# 67_Ethernet-GEPHY_RGMII0.net
KiCad netlist of a schematic drawn in Altium Designer
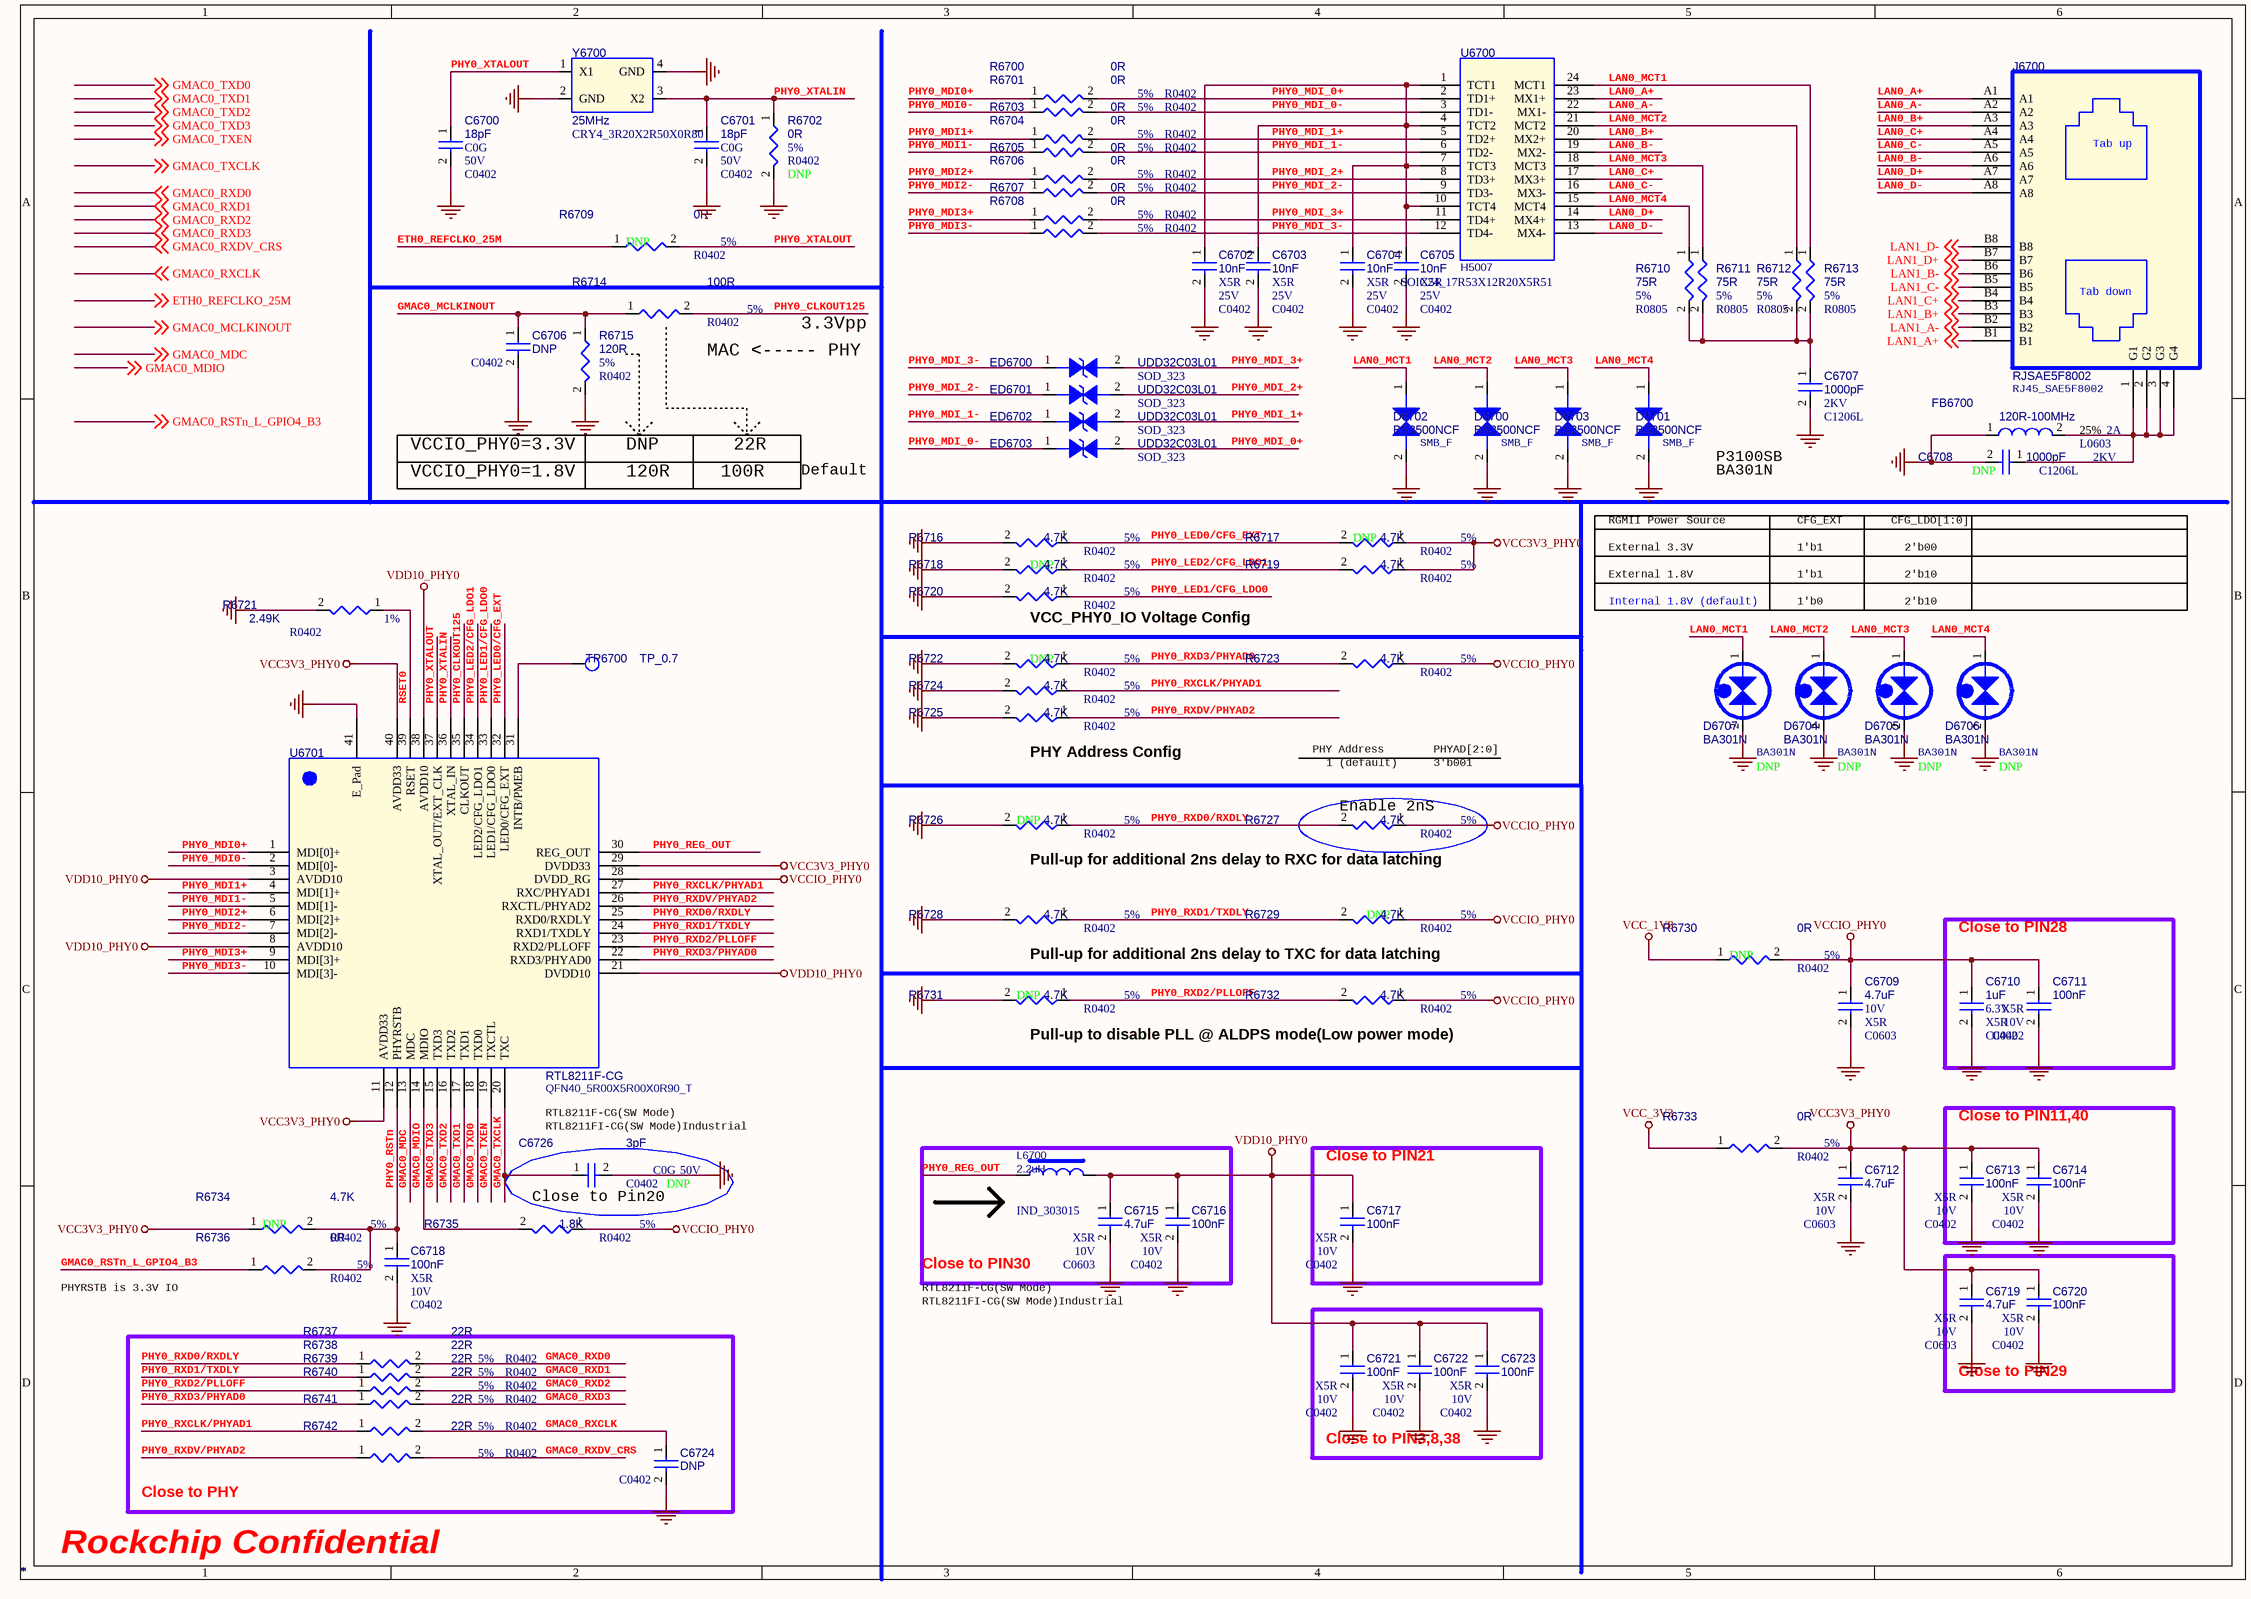
[diagram p0: 67.Ethernet-GEPHY_RGMII0.SchDoc]

(export (version "E")
  (design (tool "Eeschema 10.0.6"))
  (components
    (comp (ref "C6700")
      (value "*")
      (footprint "C0402")
      (description "cap,18.00pF,+/-5%,50V,C0G,C0402")
      (fields
        (field (name "VOLTAGE") "50V")
        (field (name "PCB FOOTPRINT") "C0402")
        (field (name "DIELECTRIC") "C0G")
        (field (name "TOLERANCE") "5%")
        (field (name "MANUFACTURER") "TDK")
        (field (name "ALTIUM_UNNAMED_1") "18pF")
        (field (name "CREATED BY") "JJJ")
      )
      (libsource (lib "*") (part "CAP NP"))
    )
    (comp (ref "C6701")
      (value "*")
      (footprint "C0402")
      (description "cap,18.00pF,+/-5%,50V,C0G,C0402")
      (fields
        (field (name "VOLTAGE") "50V")
        (field (name "PCB FOOTPRINT") "C0402")
        (field (name "DIELECTRIC") "C0G")
        (field (name "TOLERANCE") "5%")
        (field (name "MANUFACTURER") "TDK")
        (field (name "ALTIUM_UNNAMED_1") "18pF")
        (field (name "CREATED BY") "JJJ")
      )
      (libsource (lib "*") (part "CAP NP"))
    )
    (comp (ref "C6702")
      (value "*")
      (footprint "C0402")
      (description "cap,10.00nF,+/-10%,25V,X5R,C0402")
      (fields
        (field (name "VOLTAGE") "25V")
        (field (name "PCB FOOTPRINT") "C0402")
        (field (name "DIELECTRIC") "X5R")
        (field (name "TOLERANCE") "10%")
        (field (name "MANUFACTURER") "TDK")
        (field (name "ALTIUM_UNNAMED_1") "10nF")
        (field (name "CREATED BY") "JJJ")
      )
      (libsource (lib "*") (part "CAP NP"))
    )
    (comp (ref "C6703")
      (value "*")
      (footprint "C0402")
      (description "cap,10.00nF,+/-10%,25V,X5R,C0402")
      (fields
        (field (name "VOLTAGE") "25V")
        (field (name "PCB FOOTPRINT") "C0402")
        (field (name "DIELECTRIC") "X5R")
        (field (name "TOLERANCE") "10%")
        (field (name "MANUFACTURER") "TDK")
        (field (name "ALTIUM_UNNAMED_1") "10nF")
        (field (name "CREATED BY") "JJJ")
      )
      (libsource (lib "*") (part "CAP NP"))
    )
    (comp (ref "C6704")
      (value "*")
      (footprint "C0402")
      (description "cap,10.00nF,+/-10%,25V,X5R,C0402")
      (fields
        (field (name "VOLTAGE") "25V")
        (field (name "PCB FOOTPRINT") "C0402")
        (field (name "DIELECTRIC") "X5R")
        (field (name "MANUFACTURER") "TDK")
        (field (name "TOLERANCE") "10%")
        (field (name "ALTIUM_UNNAMED_1") "10nF")
        (field (name "CREATED BY") "JJJ")
      )
      (libsource (lib "*") (part "CAP NP"))
    )
    (comp (ref "C6705")
      (value "*")
      (footprint "C0402")
      (description "cap,10.00nF,+/-10%,25V,X5R,C0402")
      (fields
        (field (name "VOLTAGE") "25V")
        (field (name "PCB FOOTPRINT") "C0402")
        (field (name "DIELECTRIC") "X5R")
        (field (name "MANUFACTURER") "TDK")
        (field (name "TOLERANCE") "10%")
        (field (name "ALTIUM_UNNAMED_1") "10nF")
        (field (name "CREATED BY") "JJJ")
      )
      (libsource (lib "*") (part "CAP NP"))
    )
    (comp (ref "C6706")
      (value "*")
      (footprint "C0402")
      (description "Did Not Place.")
      (fields
        (field (name "PCB FOOTPRINT") "C0402")
        (field (name "ALTIUM_UNNAMED_1") "DNP")
        (field (name "CREATED BY") "JJJ")
      )
      (libsource (lib "*") (part "CAP NP"))
    )
    (comp (ref "C6707")
      (value "*")
      (footprint "C1206L")
      (description "ёЯС№µзИЭ,1000pF/2KV,C1206")
      (fields
        (field (name "VOLTAGE") "2KV")
        (field (name "PCB FOOTPRINT") "C1206L")
        (field (name "TOLERANCE") "20%")
        (field (name "ALTIUM_UNNAMED_1") "1000pF")
        (field (name "CREATED BY") "JJJ")
      )
      (libsource (lib "*") (part "CAP NP"))
    )
    (comp (ref "C6708")
      (value "*")
      (footprint "C1206L")
      (description "ёЯС№µзИЭ,1000pF/2KV,C1206")
      (fields
        (field (name "VOLTAGE") "2KV")
        (field (name "PCB FOOTPRINT") "C1206L")
        (field (name "TOLERANCE") "20%")
        (field (name "OPTION") "DNP")
        (field (name "ALTIUM_UNNAMED_1") "1000pF")
        (field (name "CREATED BY") "JJJ")
      )
      (libsource (lib "*") (part "CAP NP"))
    )
    (comp (ref "C6709")
      (value "*")
      (footprint "C0603")
      (description "cap,4.70uF,+/-10%,10V,X5R,C0603")
      (fields
        (field (name "VOLTAGE") "10V")
        (field (name "PCB FOOTPRINT") "C0603")
        (field (name "DIELECTRIC") "X5R")
        (field (name "TOLERANCE") "10%")
        (field (name "MANUFACTURER") "TDK")
        (field (name "ALTIUM_UNNAMED_1") "4.7uF")
        (field (name "CREATED BY") "JJJ")
      )
      (libsource (lib "*") (part "CAP NP"))
    )
    (comp (ref "C6710")
      (value "*")
      (footprint "C0402")
      (description "cap,1.00uF,+/-10%,6.3V,X5R,C0402")
      (fields
        (field (name "VOLTAGE") "6.3V")
        (field (name "PCB FOOTPRINT") "C0402")
        (field (name "DIELECTRIC") "X5R")
        (field (name "TOLERANCE") "10%")
        (field (name "MANUFACTURER") "TDK")
        (field (name "ALTIUM_UNNAMED_1") "1uF")
        (field (name "CREATED BY") "JJJ")
      )
      (libsource (lib "*") (part "CAP NP"))
    )
    (comp (ref "C6711")
      (value "*")
      (footprint "C0402")
      (description "cap,100.00nF,+/-10%,10V,X5R,C0402")
      (fields
        (field (name "VOLTAGE") "10V")
        (field (name "PCB FOOTPRINT") "C0402")
        (field (name "DIELECTRIC") "X5R")
        (field (name "TOLERANCE") "10%")
        (field (name "MANUFACTURER") "TDK")
        (field (name "ALTIUM_UNNAMED_1") "100nF")
        (field (name "CREATED BY") "JJJ")
      )
      (libsource (lib "*") (part "CAP NP"))
    )
    (comp (ref "C6712")
      (value "*")
      (footprint "C0603")
      (description "cap,4.70uF,+/-10%,10V,X5R,C0603")
      (fields
        (field (name "VOLTAGE") "10V")
        (field (name "PCB FOOTPRINT") "C0603")
        (field (name "DIELECTRIC") "X5R")
        (field (name "MANUFACTURER") "TDK")
        (field (name "TOLERANCE") "10%")
        (field (name "ALTIUM_UNNAMED_1") "4.7uF")
        (field (name "CREATED BY") "JJJ")
      )
      (libsource (lib "*") (part "CAP NP"))
    )
    (comp (ref "C6713")
      (value "*")
      (footprint "C0402")
      (description "cap,100.00nF,+/-10%,10V,X5R,C0402")
      (fields
        (field (name "VOLTAGE") "10V")
        (field (name "PCB FOOTPRINT") "C0402")
        (field (name "DIELECTRIC") "X5R")
        (field (name "TOLERANCE") "10%")
        (field (name "MANUFACTURER") "TDK")
        (field (name "ALTIUM_UNNAMED_1") "100nF")
        (field (name "CREATED BY") "JJJ")
      )
      (libsource (lib "*") (part "CAP NP"))
    )
    (comp (ref "C6714")
      (value "*")
      (footprint "C0402")
      (description "cap,100.00nF,+/-10%,10V,X5R,C0402")
      (fields
        (field (name "VOLTAGE") "10V")
        (field (name "PCB FOOTPRINT") "C0402")
        (field (name "DIELECTRIC") "X5R")
        (field (name "TOLERANCE") "10%")
        (field (name "MANUFACTURER") "TDK")
        (field (name "ALTIUM_UNNAMED_1") "100nF")
        (field (name "CREATED BY") "JJJ")
      )
      (libsource (lib "*") (part "CAP NP"))
    )
    (comp (ref "C6715")
      (value "*")
      (footprint "C0603")
      (description "cap,4.70uF,+/-10%,10V,X5R,C0603")
      (fields
        (field (name "VOLTAGE") "10V")
        (field (name "PCB FOOTPRINT") "C0603")
        (field (name "DIELECTRIC") "X5R")
        (field (name "MANUFACTURER") "TDK")
        (field (name "TOLERANCE") "10%")
        (field (name "ALTIUM_UNNAMED_1") "4.7uF")
        (field (name "CREATED BY") "JJJ")
      )
      (libsource (lib "*") (part "CAP NP"))
    )
    (comp (ref "C6716")
      (value "*")
      (footprint "C0402")
      (description "cap,100.00nF,+/-10%,10V,X5R,C0402")
      (fields
        (field (name "VOLTAGE") "10V")
        (field (name "PCB FOOTPRINT") "C0402")
        (field (name "DIELECTRIC") "X5R")
        (field (name "MANUFACTURER") "TDK")
        (field (name "TOLERANCE") "10%")
        (field (name "ALTIUM_UNNAMED_1") "100nF")
        (field (name "CREATED BY") "JJJ")
      )
      (libsource (lib "*") (part "CAP NP"))
    )
    (comp (ref "C6717")
      (value "*")
      (footprint "C0402")
      (description "cap,100.00nF,+/-10%,10V,X5R,C0402")
      (fields
        (field (name "VOLTAGE") "10V")
        (field (name "PCB FOOTPRINT") "C0402")
        (field (name "DIELECTRIC") "X5R")
        (field (name "MANUFACTURER") "TDK")
        (field (name "TOLERANCE") "10%")
        (field (name "ALTIUM_UNNAMED_1") "100nF")
        (field (name "CREATED BY") "JJJ")
      )
      (libsource (lib "*") (part "CAP NP"))
    )
    (comp (ref "C6718")
      (value "*")
      (footprint "C0402")
      (description "cap,100.00nF,+/-10%,10V,X5R,C0402")
      (fields
        (field (name "VOLTAGE") "10V")
        (field (name "PCB FOOTPRINT") "C0402")
        (field (name "DIELECTRIC") "X5R")
        (field (name "MANUFACTURER") "TDK")
        (field (name "TOLERANCE") "10%")
        (field (name "ALTIUM_UNNAMED_1") "100nF")
        (field (name "CREATED BY") "JJJ")
      )
      (libsource (lib "*") (part "CAP NP"))
    )
    (comp (ref "C6719")
      (value "*")
      (footprint "C0603")
      (description "cap,4.70uF,+/-10%,10V,X5R,C0603")
      (fields
        (field (name "VOLTAGE") "10V")
        (field (name "PCB FOOTPRINT") "C0603")
        (field (name "DIELECTRIC") "X5R")
        (field (name "MANUFACTURER") "TDK")
        (field (name "TOLERANCE") "10%")
        (field (name "ALTIUM_UNNAMED_1") "4.7uF")
        (field (name "CREATED BY") "JJJ")
      )
      (libsource (lib "*") (part "CAP NP"))
    )
    (comp (ref "C6720")
      (value "*")
      (footprint "C0402")
      (description "cap,100.00nF,+/-10%,10V,X5R,C0402")
      (fields
        (field (name "VOLTAGE") "10V")
        (field (name "PCB FOOTPRINT") "C0402")
        (field (name "DIELECTRIC") "X5R")
        (field (name "TOLERANCE") "10%")
        (field (name "MANUFACTURER") "TDK")
        (field (name "ALTIUM_UNNAMED_1") "100nF")
        (field (name "CREATED BY") "JJJ")
      )
      (libsource (lib "*") (part "CAP NP"))
    )
    (comp (ref "C6721")
      (value "*")
      (footprint "C0402")
      (description "cap,100.00nF,+/-10%,10V,X5R,C0402")
      (fields
        (field (name "VOLTAGE") "10V")
        (field (name "PCB FOOTPRINT") "C0402")
        (field (name "DIELECTRIC") "X5R")
        (field (name "TOLERANCE") "10%")
        (field (name "MANUFACTURER") "TDK")
        (field (name "ALTIUM_UNNAMED_1") "100nF")
        (field (name "CREATED BY") "JJJ")
      )
      (libsource (lib "*") (part "CAP NP"))
    )
    (comp (ref "C6722")
      (value "*")
      (footprint "C0402")
      (description "cap,100.00nF,+/-10%,10V,X5R,C0402")
      (fields
        (field (name "VOLTAGE") "10V")
        (field (name "PCB FOOTPRINT") "C0402")
        (field (name "DIELECTRIC") "X5R")
        (field (name "TOLERANCE") "10%")
        (field (name "MANUFACTURER") "TDK")
        (field (name "ALTIUM_UNNAMED_1") "100nF")
        (field (name "CREATED BY") "JJJ")
      )
      (libsource (lib "*") (part "CAP NP"))
    )
    (comp (ref "C6723")
      (value "*")
      (footprint "C0402")
      (description "cap,100.00nF,+/-10%,10V,X5R,C0402")
      (fields
        (field (name "VOLTAGE") "10V")
        (field (name "PCB FOOTPRINT") "C0402")
        (field (name "DIELECTRIC") "X5R")
        (field (name "TOLERANCE") "10%")
        (field (name "MANUFACTURER") "TDK")
        (field (name "ALTIUM_UNNAMED_1") "100nF")
        (field (name "CREATED BY") "JJJ")
      )
      (libsource (lib "*") (part "CAP NP"))
    )
    (comp (ref "C6724")
      (value "*")
      (footprint "C0402")
      (description "Did Not Place.")
      (fields
        (field (name "PCB FOOTPRINT") "C0402")
        (field (name "ALTIUM_UNNAMED_1") "DNP")
        (field (name "CREATED BY") "JJJ")
      )
      (libsource (lib "*") (part "CAP NP"))
    )
    (comp (ref "C6726")
      (value "*")
      (footprint "C0402")
      (description "cap,3.00pF,+/-0.25,50V,C0G,C0402")
      (fields
        (field (name "VOLTAGE") "50V")
        (field (name "PCB FOOTPRINT") "C0402")
        (field (name "DIELECTRIC") "C0G")
        (field (name "TOLERANCE") "+/-0.25pF")
        (field (name "MANUFACTURER") "TDK")
        (field (name "OPTION") "DNP")
        (field (name "ALTIUM_UNNAMED_1") "3pF")
        (field (name "CREATED BY") "JJJ")
      )
      (libsource (lib "*") (part "CAP NP"))
    )
    (comp (ref "D6700")
      (value "*")
      (footprint "BA301N")
      (fields (field (name "PCB FOOTPRINT") "SMB_F") (field (name "ALTIUM_UNNAMED_1") "BS3500NCF"))
      (libsource (lib "*") (part "BA301N_3"))
    )
    (comp (ref "D6701")
      (value "*")
      (footprint "BA301N")
      (fields (field (name "PCB FOOTPRINT") "SMB_F") (field (name "ALTIUM_UNNAMED_1") "BS3500NCF"))
      (libsource (lib "*") (part "BA301N_3"))
    )
    (comp (ref "D6702")
      (value "*")
      (footprint "BA301N")
      (fields (field (name "PCB FOOTPRINT") "SMB_F") (field (name "ALTIUM_UNNAMED_1") "BS3500NCF"))
      (libsource (lib "*") (part "BA301N_3"))
    )
    (comp (ref "D6703")
      (value "*")
      (footprint "BA301N")
      (fields (field (name "PCB FOOTPRINT") "SMB_F") (field (name "ALTIUM_UNNAMED_1") "BS3500NCF"))
      (libsource (lib "*") (part "BA301N_3"))
    )
    (comp (ref "D6704")
      (value "*")
      (footprint "BA301N")
      (fields
        (field (name "OPTION") "DNP")
        (field (name "PCB FOOTPRINT") "BA301N")
        (field (name "ALTIUM_UNNAMED_1") "BA301N")
      )
      (libsource (lib "*") (part "BA301N_1"))
    )
    (comp (ref "D6705")
      (value "*")
      (footprint "BA301N")
      (fields
        (field (name "OPTION") "DNP")
        (field (name "PCB FOOTPRINT") "BA301N")
        (field (name "ALTIUM_UNNAMED_1") "BA301N")
      )
      (libsource (lib "*") (part "BA301N_1"))
    )
    (comp (ref "D6706")
      (value "*")
      (footprint "BA301N")
      (fields
        (field (name "OPTION") "DNP")
        (field (name "PCB FOOTPRINT") "BA301N")
        (field (name "ALTIUM_UNNAMED_1") "BA301N")
      )
      (libsource (lib "*") (part "BA301N_1"))
    )
    (comp (ref "D6707")
      (value "*")
      (footprint "BA301N")
      (fields
        (field (name "OPTION") "DNP")
        (field (name "PCB FOOTPRINT") "BA301N")
        (field (name "ALTIUM_UNNAMED_1") "BA301N")
      )
      (libsource (lib "*") (part "BA301N_1"))
    )
    (comp (ref "ED6700")
      (value "*")
      (footprint "SOD_323")
      (description "Transient Voltage Suppressor,0.8pF")
      (fields
        (field (name "PCB FOOTPRINT") "SOD_323")
        (field (name "MANUFACTURER") "WillSemi(О¤¶ы°лµјМе)")
        (field (name "ALTIUM_UNNAMED_1") "UDD32C03L01")
        (field (name "CREATED BY") "JJJ")
      )
      (libsource (lib "*") (part "DIODE BI_DIR TRIG"))
    )
    (comp (ref "ED6701")
      (value "*")
      (footprint "SOD_323")
      (description "Transient Voltage Suppressor,0.8pF")
      (fields
        (field (name "PCB FOOTPRINT") "SOD_323")
        (field (name "MANUFACTURER") "WillSemi(О¤¶ы°лµјМе)")
        (field (name "ALTIUM_UNNAMED_1") "UDD32C03L01")
        (field (name "CREATED BY") "JJJ")
      )
      (libsource (lib "*") (part "DIODE BI_DIR TRIG"))
    )
    (comp (ref "ED6702")
      (value "*")
      (footprint "SOD_323")
      (description "Transient Voltage Suppressor,0.8pF")
      (fields
        (field (name "PCB FOOTPRINT") "SOD_323")
        (field (name "MANUFACTURER") "WillSemi(О¤¶ы°лµјМе)")
        (field (name "ALTIUM_UNNAMED_1") "UDD32C03L01")
        (field (name "CREATED BY") "JJJ")
      )
      (libsource (lib "*") (part "DIODE BI_DIR TRIG"))
    )
    (comp (ref "ED6703")
      (value "*")
      (footprint "SOD_323")
      (description "Transient Voltage Suppressor,0.8pF")
      (fields
        (field (name "PCB FOOTPRINT") "SOD_323")
        (field (name "MANUFACTURER") "WillSemi(О¤¶ы°лµјМе)")
        (field (name "ALTIUM_UNNAMED_1") "UDD32C03L01")
        (field (name "CREATED BY") "JJJ")
      )
      (libsource (lib "*") (part "DIODE BI_DIR TRIG"))
    )
    (comp (ref "FB6700")
      (value "*")
      (footprint "L0603")
      (description "BEAD,120R@100MHz,current=2000mA,0603")
      (fields
        (field (name "TOLERANCE") "25%")
        (field (name "PCB FOOTPRINT") "L0603")
        (field (name "IRMS") "2A")
        (field (name "MANUFACTURER") "Murata")
        (field (name "ALTIUM_UNNAMED_1") "120R-100MHz")
        (field (name "CREATED BY") "DZS")
      )
      (libsource (lib "*") (part "BEAD"))
    )
    (comp (ref "J6700")
      (value "*")
      (footprint "RJSAE5F8002")
      (fields (field (name "PCB FOOTPRINT") "RJ45_SAE5F8002") (field (name "ALTIUM_UNNAMED_1") "RJSAE5F8002"))
      (libsource (lib "*") (part "RJSAE5F8002"))
    )
    (comp (ref "L6700")
      (value "*")
      (footprint "IND_303015")
      (description "Power Inductor,2.2uH,0.3,IND_303015")
      (fields
        (field (name "PCB FOOTPRINT") "IND_303015")
        (field (name "MANUFACTURER") "sunlord")
        (field (name "TOLERANCE") "30%")
        (field (name "ALTIUM_UNNAMED_1") "2.2uH")
        (field (name "CREATED BY") "YTL")
      )
      (libsource (lib "*") (part "INDUCTORS OF FERRITE_Dup1"))
    )
    (comp (ref "R6700")
      (value "*")
      (footprint "R0402")
      (description "НЁУГєсД¤µзЧи,0R,+/-5%,R0402,1/16W.")
      (fields
        (field (name "PCB FOOTPRINT") "R0402")
        (field (name "TOLERANCE") "5%")
        (field (name "MANUFACTURER") "YAGEO")
        (field (name "ALTIUM_UNNAMED_1") "0R")
        (field (name "CREATED BY") "YTL")
      )
      (libsource (lib "*") (part "RESISTOR_Dup1"))
    )
    (comp (ref "R6701")
      (value "*")
      (footprint "R0402")
      (description "НЁУГєсД¤µзЧи,0R,+/-5%,R0402,1/16W.")
      (fields
        (field (name "PCB FOOTPRINT") "R0402")
        (field (name "TOLERANCE") "5%")
        (field (name "MANUFACTURER") "YAGEO")
        (field (name "ALTIUM_UNNAMED_1") "0R")
        (field (name "CREATED BY") "YTL")
      )
      (libsource (lib "*") (part "RESISTOR_Dup1"))
    )
    (comp (ref "R6702")
      (value "*")
      (footprint "R0402")
      (description "НЁУГєсД¤µзЧи,0R,+/-5%,R0402,1/16W.")
      (fields
        (field (name "PCB FOOTPRINT") "R0402")
        (field (name "TOLERANCE") "5%")
        (field (name "MANUFACTURER") "YAGEO")
        (field (name "OPTION") "DNP")
        (field (name "ALTIUM_UNNAMED_1") "0R")
        (field (name "CREATED BY") "YTL")
      )
      (libsource (lib "*") (part "RESISTOR_Dup1"))
    )
    (comp (ref "R6703")
      (value "*")
      (footprint "R0402")
      (description "НЁУГєсД¤µзЧи,0R,+/-5%,R0402,1/16W.")
      (fields
        (field (name "PCB FOOTPRINT") "R0402")
        (field (name "TOLERANCE") "5%")
        (field (name "MANUFACTURER") "YAGEO")
        (field (name "ALTIUM_UNNAMED_1") "0R")
        (field (name "CREATED BY") "YTL")
      )
      (libsource (lib "*") (part "RESISTOR_Dup1"))
    )
    (comp (ref "R6704")
      (value "*")
      (footprint "R0402")
      (description "НЁУГєсД¤µзЧи,0R,+/-5%,R0402,1/16W.")
      (fields
        (field (name "PCB FOOTPRINT") "R0402")
        (field (name "TOLERANCE") "5%")
        (field (name "MANUFACTURER") "YAGEO")
        (field (name "ALTIUM_UNNAMED_1") "0R")
        (field (name "CREATED BY") "YTL")
      )
      (libsource (lib "*") (part "RESISTOR_Dup1"))
    )
    (comp (ref "R6705")
      (value "*")
      (footprint "R0402")
      (description "НЁУГєсД¤µзЧи,0R,+/-5%,R0402,1/16W.")
      (fields
        (field (name "PCB FOOTPRINT") "R0402")
        (field (name "TOLERANCE") "5%")
        (field (name "MANUFACTURER") "YAGEO")
        (field (name "ALTIUM_UNNAMED_1") "0R")
        (field (name "CREATED BY") "YTL")
      )
      (libsource (lib "*") (part "RESISTOR_Dup1"))
    )
    (comp (ref "R6706")
      (value "*")
      (footprint "R0402")
      (description "НЁУГєсД¤µзЧи,0R,+/-5%,R0402,1/16W.")
      (fields
        (field (name "PCB FOOTPRINT") "R0402")
        (field (name "TOLERANCE") "5%")
        (field (name "MANUFACTURER") "YAGEO")
        (field (name "ALTIUM_UNNAMED_1") "0R")
        (field (name "CREATED BY") "YTL")
      )
      (libsource (lib "*") (part "RESISTOR_Dup1"))
    )
    (comp (ref "R6707")
      (value "*")
      (footprint "R0402")
      (description "НЁУГєсД¤µзЧи,0R,+/-5%,R0402,1/16W.")
      (fields
        (field (name "PCB FOOTPRINT") "R0402")
        (field (name "TOLERANCE") "5%")
        (field (name "MANUFACTURER") "YAGEO")
        (field (name "ALTIUM_UNNAMED_1") "0R")
        (field (name "CREATED BY") "YTL")
      )
      (libsource (lib "*") (part "RESISTOR_Dup1"))
    )
    (comp (ref "R6708")
      (value "*")
      (footprint "R0402")
      (description "НЁУГєсД¤µзЧи,0R,+/-5%,R0402,1/16W.")
      (fields
        (field (name "PCB FOOTPRINT") "R0402")
        (field (name "TOLERANCE") "5%")
        (field (name "MANUFACTURER") "YAGEO")
        (field (name "ALTIUM_UNNAMED_1") "0R")
        (field (name "CREATED BY") "YTL")
      )
      (libsource (lib "*") (part "RESISTOR_Dup1"))
    )
    (comp (ref "R6709")
      (value "*")
      (footprint "R0402")
      (description "НЁУГєсД¤µзЧи,0R,+/-5%,R0402,1/16W.")
      (fields
        (field (name "PCB FOOTPRINT") "R0402")
        (field (name "TOLERANCE") "5%")
        (field (name "OPTION") "DNP")
        (field (name "MANUFACTURER") "YAGEO")
        (field (name "ALTIUM_UNNAMED_1") "0R")
        (field (name "CREATED BY") "YTL")
      )
      (libsource (lib "*") (part "RESISTOR_Dup1"))
    )
    (comp (ref "R6710")
      (value "*")
      (footprint "R0402")
      (description "НЁУГєсД¤µзЧи,75R,+/-5%,R0805,1/8W.")
      (fields
        (field (name "PCB FOOTPRINT") "R0805")
        (field (name "TOLERANCE") "5%")
        (field (name "MANUFACTURER") "YAGEO")
        (field (name "ALTIUM_UNNAMED_1") "75R")
        (field (name "CREATED BY") "YTL")
      )
      (libsource (lib "*") (part "RESISTOR_Dup1"))
    )
    (comp (ref "R6711")
      (value "*")
      (footprint "R0402")
      (description "НЁУГєсД¤µзЧи,75R,+/-5%,R0805,1/8W.")
      (fields
        (field (name "PCB FOOTPRINT") "R0805")
        (field (name "TOLERANCE") "5%")
        (field (name "MANUFACTURER") "YAGEO")
        (field (name "ALTIUM_UNNAMED_1") "75R")
        (field (name "CREATED BY") "YTL")
      )
      (libsource (lib "*") (part "RESISTOR_Dup1"))
    )
    (comp (ref "R6712")
      (value "*")
      (footprint "R0402")
      (description "НЁУГєсД¤µзЧи,75R,+/-5%,R0805,1/8W.")
      (fields
        (field (name "PCB FOOTPRINT") "R0805")
        (field (name "TOLERANCE") "5%")
        (field (name "MANUFACTURER") "YAGEO")
        (field (name "ALTIUM_UNNAMED_1") "75R")
        (field (name "CREATED BY") "YTL")
      )
      (libsource (lib "*") (part "RESISTOR_Dup1"))
    )
    (comp (ref "R6713")
      (value "*")
      (footprint "R0402")
      (description "НЁУГєсД¤µзЧи,75R,+/-5%,R0805,1/8W.")
      (fields
        (field (name "PCB FOOTPRINT") "R0805")
        (field (name "TOLERANCE") "5%")
        (field (name "MANUFACTURER") "YAGEO")
        (field (name "ALTIUM_UNNAMED_1") "75R")
        (field (name "CREATED BY") "YTL")
      )
      (libsource (lib "*") (part "RESISTOR_Dup1"))
    )
    (comp (ref "R6714")
      (value "*")
      (footprint "R0402")
      (description "НЁУГєсД¤µзЧи,100R,+/-5%,R0402,1/16W.")
      (fields
        (field (name "PCB FOOTPRINT") "R0402")
        (field (name "TOLERANCE") "5%")
        (field (name "MANUFACTURER") "YAGEO")
        (field (name "ALTIUM_UNNAMED_1") "100R")
        (field (name "CREATED BY") "YTL")
      )
      (libsource (lib "*") (part "RESISTOR_Dup1"))
    )
    (comp (ref "R6715")
      (value "*")
      (footprint "R0402")
      (description "НЁУГєсД¤µзЧи,120R,+/-5%,R0402,1/16W.")
      (fields
        (field (name "PCB FOOTPRINT") "R0402")
        (field (name "TOLERANCE") "5%")
        (field (name "MANUFACTURER") "YAGEO")
        (field (name "ALTIUM_UNNAMED_1") "120R")
        (field (name "CREATED BY") "YTL")
      )
      (libsource (lib "*") (part "RESISTOR_Dup1"))
    )
    (comp (ref "R6716")
      (value "*")
      (footprint "R0402")
      (description "НЁУГєсД¤µзЧи,4K7,+/-5%,R0402,1/16W.")
      (fields
        (field (name "PCB FOOTPRINT") "R0402")
        (field (name "TOLERANCE") "5%")
        (field (name "MANUFACTURER") "YAGEO")
        (field (name "ALTIUM_UNNAMED_1") "4.7K")
        (field (name "CREATED BY") "YTL")
      )
      (libsource (lib "*") (part "RESISTOR_Dup1"))
    )
    (comp (ref "R6717")
      (value "*")
      (footprint "R0402")
      (description "НЁУГєсД¤µзЧи,4K7,+/-5%,R0402,1/16W.")
      (fields
        (field (name "PCB FOOTPRINT") "R0402")
        (field (name "TOLERANCE") "5%")
        (field (name "MANUFACTURER") "YAGEO")
        (field (name "OPTION") "DNP")
        (field (name "ALTIUM_UNNAMED_1") "4.7K")
        (field (name "CREATED BY") "YTL")
      )
      (libsource (lib "*") (part "RESISTOR_Dup1"))
    )
    (comp (ref "R6718")
      (value "*")
      (footprint "R0402")
      (description "НЁУГєсД¤µзЧи,4K7,+/-5%,R0402,1/16W.")
      (fields
        (field (name "PCB FOOTPRINT") "R0402")
        (field (name "TOLERANCE") "5%")
        (field (name "OPTION") "DNP")
        (field (name "MANUFACTURER") "YAGEO")
        (field (name "ALTIUM_UNNAMED_1") "4.7K")
        (field (name "CREATED BY") "YTL")
      )
      (libsource (lib "*") (part "RESISTOR_Dup1"))
    )
    (comp (ref "R6719")
      (value "*")
      (footprint "R0402")
      (description "НЁУГєсД¤µзЧи,4K7,+/-5%,R0402,1/16W.")
      (fields
        (field (name "PCB FOOTPRINT") "R0402")
        (field (name "TOLERANCE") "5%")
        (field (name "MANUFACTURER") "YAGEO")
        (field (name "ALTIUM_UNNAMED_1") "4.7K")
        (field (name "CREATED BY") "YTL")
      )
      (libsource (lib "*") (part "RESISTOR_Dup1"))
    )
    (comp (ref "R6720")
      (value "*")
      (footprint "R0402")
      (description "НЁУГєсД¤µзЧи,4K7,+/-5%,R0402,1/16W.")
      (fields
        (field (name "PCB FOOTPRINT") "R0402")
        (field (name "TOLERANCE") "5%")
        (field (name "MANUFACTURER") "YAGEO")
        (field (name "ALTIUM_UNNAMED_1") "4.7K")
        (field (name "CREATED BY") "YTL")
      )
      (libsource (lib "*") (part "RESISTOR_Dup1"))
    )
    (comp (ref "R6721")
      (value "*")
      (footprint "R0402")
      (description "НЁУГєсД¤µзЧи,2K49,+/-1%,R0402,1/16W.")
      (fields
        (field (name "PCB FOOTPRINT") "R0402")
        (field (name "TOLERANCE") "1%")
        (field (name "MANUFACTURER") "YAGEO")
        (field (name "ALTIUM_UNNAMED_1") "2.49K")
        (field (name "CREATED BY") "YTL")
      )
      (libsource (lib "*") (part "RESISTOR_Dup1"))
    )
    (comp (ref "R6722")
      (value "*")
      (footprint "R0402")
      (description "НЁУГєсД¤µзЧи,4K7,+/-5%,R0402,1/16W.")
      (fields
        (field (name "PCB FOOTPRINT") "R0402")
        (field (name "TOLERANCE") "5%")
        (field (name "OPTION") "DNP")
        (field (name "MANUFACTURER") "YAGEO")
        (field (name "ALTIUM_UNNAMED_1") "4.7K")
        (field (name "CREATED BY") "YTL")
      )
      (libsource (lib "*") (part "RESISTOR_Dup1"))
    )
    (comp (ref "R6723")
      (value "*")
      (footprint "R0402")
      (description "НЁУГєсД¤µзЧи,4K7,+/-5%,R0402,1/16W.")
      (fields
        (field (name "PCB FOOTPRINT") "R0402")
        (field (name "TOLERANCE") "5%")
        (field (name "MANUFACTURER") "YAGEO")
        (field (name "ALTIUM_UNNAMED_1") "4.7K")
        (field (name "CREATED BY") "YTL")
      )
      (libsource (lib "*") (part "RESISTOR_Dup1"))
    )
    (comp (ref "R6724")
      (value "*")
      (footprint "R0402")
      (description "НЁУГєсД¤µзЧи,4K7,+/-5%,R0402,1/16W.")
      (fields
        (field (name "PCB FOOTPRINT") "R0402")
        (field (name "TOLERANCE") "5%")
        (field (name "MANUFACTURER") "YAGEO")
        (field (name "ALTIUM_UNNAMED_1") "4.7K")
        (field (name "CREATED BY") "YTL")
      )
      (libsource (lib "*") (part "RESISTOR_Dup1"))
    )
    (comp (ref "R6725")
      (value "*")
      (footprint "R0402")
      (description "НЁУГєсД¤µзЧи,4K7,+/-5%,R0402,1/16W.")
      (fields
        (field (name "PCB FOOTPRINT") "R0402")
        (field (name "TOLERANCE") "5%")
        (field (name "MANUFACTURER") "YAGEO")
        (field (name "ALTIUM_UNNAMED_1") "4.7K")
        (field (name "CREATED BY") "YTL")
      )
      (libsource (lib "*") (part "RESISTOR_Dup1"))
    )
    (comp (ref "R6726")
      (value "*")
      (footprint "R0402")
      (description "НЁУГєсД¤µзЧи,4K7,+/-5%,R0402,1/16W.")
      (fields
        (field (name "PCB FOOTPRINT") "R0402")
        (field (name "TOLERANCE") "5%")
        (field (name "OPTION") "DNP")
        (field (name "MANUFACTURER") "YAGEO")
        (field (name "ALTIUM_UNNAMED_1") "4.7K")
        (field (name "CREATED BY") "YTL")
      )
      (libsource (lib "*") (part "RESISTOR_Dup1"))
    )
    (comp (ref "R6727")
      (value "*")
      (footprint "R0402")
      (description "НЁУГєсД¤µзЧи,4K7,+/-5%,R0402,1/16W.")
      (fields
        (field (name "PCB FOOTPRINT") "R0402")
        (field (name "TOLERANCE") "5%")
        (field (name "MANUFACTURER") "YAGEO")
        (field (name "ALTIUM_UNNAMED_1") "4.7K")
        (field (name "CREATED BY") "YTL")
      )
      (libsource (lib "*") (part "RESISTOR_Dup1"))
    )
    (comp (ref "R6728")
      (value "*")
      (footprint "R0402")
      (description "НЁУГєсД¤µзЧи,4K7,+/-5%,R0402,1/16W.")
      (fields
        (field (name "PCB FOOTPRINT") "R0402")
        (field (name "TOLERANCE") "5%")
        (field (name "MANUFACTURER") "YAGEO")
        (field (name "ALTIUM_UNNAMED_1") "4.7K")
        (field (name "CREATED BY") "YTL")
      )
      (libsource (lib "*") (part "RESISTOR_Dup1"))
    )
    (comp (ref "R6729")
      (value "*")
      (footprint "R0402")
      (description "НЁУГєсД¤µзЧи,4K7,+/-5%,R0402,1/16W.")
      (fields
        (field (name "PCB FOOTPRINT") "R0402")
        (field (name "TOLERANCE") "5%")
        (field (name "MANUFACTURER") "YAGEO")
        (field (name "OPTION") "DNP")
        (field (name "ALTIUM_UNNAMED_1") "4.7K")
        (field (name "CREATED BY") "YTL")
      )
      (libsource (lib "*") (part "RESISTOR_Dup1"))
    )
    (comp (ref "R6730")
      (value "*")
      (footprint "R0402")
      (description "НЁУГєсД¤µзЧи,0R,+/-5%,R0402,1/16W.")
      (fields
        (field (name "PCB FOOTPRINT") "R0402")
        (field (name "TOLERANCE") "5%")
        (field (name "MANUFACTURER") "YAGEO")
        (field (name "OPTION") "DNP")
        (field (name "ALTIUM_UNNAMED_1") "0R")
        (field (name "CREATED BY") "YTL")
      )
      (libsource (lib "*") (part "RESISTOR_Dup1"))
    )
    (comp (ref "R6731")
      (value "*")
      (footprint "R0402")
      (description "НЁУГєсД¤µзЧи,4K7,+/-5%,R0402,1/16W.")
      (fields
        (field (name "PCB FOOTPRINT") "R0402")
        (field (name "TOLERANCE") "5%")
        (field (name "MANUFACTURER") "YAGEO")
        (field (name "OPTION") "DNP")
        (field (name "ALTIUM_UNNAMED_1") "4.7K")
        (field (name "CREATED BY") "YTL")
      )
      (libsource (lib "*") (part "RESISTOR_Dup1"))
    )
    (comp (ref "R6732")
      (value "*")
      (footprint "R0402")
      (description "НЁУГєсД¤µзЧи,4K7,+/-5%,R0402,1/16W.")
      (fields
        (field (name "PCB FOOTPRINT") "R0402")
        (field (name "TOLERANCE") "5%")
        (field (name "MANUFACTURER") "YAGEO")
        (field (name "ALTIUM_UNNAMED_1") "4.7K")
        (field (name "CREATED BY") "YTL")
      )
      (libsource (lib "*") (part "RESISTOR_Dup1"))
    )
    (comp (ref "R6733")
      (value "*")
      (footprint "R0402")
      (description "НЁУГєсД¤µзЧи,0R,+/-5%,R0402,1/16W.")
      (fields
        (field (name "PCB FOOTPRINT") "R0402")
        (field (name "TOLERANCE") "5%")
        (field (name "MANUFACTURER") "YAGEO")
        (field (name "ALTIUM_UNNAMED_1") "0R")
        (field (name "CREATED BY") "YTL")
      )
      (libsource (lib "*") (part "RESISTOR_Dup1"))
    )
    (comp (ref "R6734")
      (value "*")
      (footprint "R0402")
      (description "НЁУГєсД¤µзЧи,4K7,+/-5%,R0402,1/16W.")
      (fields
        (field (name "PCB FOOTPRINT") "R0402")
        (field (name "TOLERANCE") "5%")
        (field (name "MANUFACTURER") "YAGEO")
        (field (name "OPTION") "DNP")
        (field (name "ALTIUM_UNNAMED_1") "4.7K")
        (field (name "CREATED BY") "YTL")
      )
      (libsource (lib "*") (part "RESISTOR_Dup1"))
    )
    (comp (ref "R6735")
      (value "*")
      (footprint "R0402")
      (description "НЁУГєсД¤µзЧи,1K8,+/-5%,R0402,1/16W.")
      (fields
        (field (name "PCB FOOTPRINT") "R0402")
        (field (name "TOLERANCE") "5%")
        (field (name "MANUFACTURER") "YAGEO")
        (field (name "ALTIUM_UNNAMED_1") "1.8K")
        (field (name "CREATED BY") "YTL")
      )
      (libsource (lib "*") (part "RESISTOR_Dup1"))
    )
    (comp (ref "R6736")
      (value "*")
      (footprint "R0402")
      (description "НЁУГєсД¤µзЧи,0R,+/-5%,R0402,1/16W.")
      (fields
        (field (name "PCB FOOTPRINT") "R0402")
        (field (name "TOLERANCE") "5%")
        (field (name "MANUFACTURER") "YAGEO")
        (field (name "ALTIUM_UNNAMED_1") "0R")
        (field (name "CREATED BY") "YTL")
      )
      (libsource (lib "*") (part "RESISTOR_Dup1"))
    )
    (comp (ref "R6737")
      (value "*")
      (footprint "R0402")
      (description "НЁУГєсД¤µзЧи,22R,+/-5%,R0402,1/16W.")
      (fields
        (field (name "PCB FOOTPRINT") "R0402")
        (field (name "TOLERANCE") "5%")
        (field (name "MANUFACTURER") "YAGEO")
        (field (name "ALTIUM_UNNAMED_1") "22R")
        (field (name "CREATED BY") "YTL")
      )
      (libsource (lib "*") (part "RESISTOR_Dup1"))
    )
    (comp (ref "R6738")
      (value "*")
      (footprint "R0402")
      (description "НЁУГєсД¤µзЧи,22R,+/-5%,R0402,1/16W.")
      (fields
        (field (name "PCB FOOTPRINT") "R0402")
        (field (name "TOLERANCE") "5%")
        (field (name "MANUFACTURER") "YAGEO")
        (field (name "ALTIUM_UNNAMED_1") "22R")
        (field (name "CREATED BY") "YTL")
      )
      (libsource (lib "*") (part "RESISTOR_Dup1"))
    )
    (comp (ref "R6739")
      (value "*")
      (footprint "R0402")
      (description "НЁУГєсД¤µзЧи,22R,+/-5%,R0402,1/16W.")
      (fields
        (field (name "PCB FOOTPRINT") "R0402")
        (field (name "TOLERANCE") "5%")
        (field (name "MANUFACTURER") "YAGEO")
        (field (name "ALTIUM_UNNAMED_1") "22R")
        (field (name "CREATED BY") "YTL")
      )
      (libsource (lib "*") (part "RESISTOR_Dup1"))
    )
    (comp (ref "R6740")
      (value "*")
      (footprint "R0402")
      (description "НЁУГєсД¤µзЧи,22R,+/-5%,R0402,1/16W.")
      (fields
        (field (name "PCB FOOTPRINT") "R0402")
        (field (name "TOLERANCE") "5%")
        (field (name "MANUFACTURER") "YAGEO")
        (field (name "ALTIUM_UNNAMED_1") "22R")
        (field (name "CREATED BY") "YTL")
      )
      (libsource (lib "*") (part "RESISTOR_Dup1"))
    )
    (comp (ref "R6741")
      (value "*")
      (footprint "R0402")
      (description "НЁУГєсД¤µзЧи,22R,+/-5%,R0402,1/16W.")
      (fields
        (field (name "PCB FOOTPRINT") "R0402")
        (field (name "TOLERANCE") "5%")
        (field (name "MANUFACTURER") "YAGEO")
        (field (name "ALTIUM_UNNAMED_1") "22R")
        (field (name "CREATED BY") "YTL")
      )
      (libsource (lib "*") (part "RESISTOR_Dup1"))
    )
    (comp (ref "R6742")
      (value "*")
      (footprint "R0402")
      (description "НЁУГєсД¤µзЧи,22R,+/-5%,R0402,1/16W.")
      (fields
        (field (name "PCB FOOTPRINT") "R0402")
        (field (name "TOLERANCE") "5%")
        (field (name "MANUFACTURER") "YAGEO")
        (field (name "ALTIUM_UNNAMED_1") "22R")
        (field (name "CREATED BY") "YTL")
      )
      (libsource (lib "*") (part "RESISTOR_Dup1"))
    )
    (comp (ref "TP6700")
      (value "*")
      (footprint "TEST")
      (description "Test Point 0.7mm")
      (fields (field (name "ALTIUM_UNNAMED_1") "TP_0.7") (field (name "CREATED BY") "JJJ"))
      (libsource (lib "*") (part "TP"))
    )
    (comp (ref "U6700")
      (value "*")
      (footprint "SOIC24_17R53X12R20X5R51")
      (description "Gigabit Ethernet (1000Base-T)")
      (fields
        (field (name "PCB FOOTPRINT") "SOIC24_17R53X12R20X5R51")
        (field (name "MANUFACTURER") "Pulse")
        (field (name "ALTIUM_UNNAMED_1") "H5007")
        (field (name "CREATED BY") "JJJ")
      )
      (libsource (lib "*") (part "Ethernet_H5007"))
    )
    (comp (ref "U6701")
      (value "*")
      (footprint "QFN40_5R00X5R00X0R80_T")
      (description "Integrated 10/100/1000 Gigabit Ethernet TransceiverЈ¬Supports IEEE 802.3az-2010,")
      (fields
        (field (name "PCB FOOTPRINT") "QFN40_5R00X5R00X0R90_T")
        (field (name "MANUFACTURER") "RealTek(ИркЕ)")
        (field (name "ALTIUM_UNNAMED_1") "RTL8211F-CG")
        (field (name "CREATED BY") "JJJ")
      )
      (libsource (lib "*") (part "Ethernet_RTL8211F"))
    )
    (comp (ref "Y6700")
      (value "*")
      (footprint "CRY-3225")
      (description "ОЮФґѕ§ХсЈ¬25MЈ¬3225,ЎА10ppmЈ¬10pFЈ¬Hosonic")
      (fields
        (field (name "PCB FOOTPRINT") "CRY4_3R20X2R50X0R80")
        (field (name "MANUFACTURER") "Hosonic(єиРЗµзЧУ)")
        (field (name "ALTIUM_UNNAMED_1") "25MHz")
        (field (name "CREATED BY") "JJJ")
      )
      (libsource (lib "*") (part "CRYSTAL_4P"))
    )
  )
  (nets
    (net (code "1") (name "/LAN0_A+") (class "Default")
      (node (ref "J6700") (pin "A1") (pinfunction "A1_A1") (pintype "passive"))
      (node (ref "U6700") (pin "23") (pinfunction "MX1+_23") (pintype "passive"))
    )
    (net (code "2") (name "/LAN0_A-") (class "Default")
      (node (ref "J6700") (pin "A2") (pinfunction "A2_A2") (pintype "passive"))
      (node (ref "U6700") (pin "22") (pinfunction "MX1-_22") (pintype "passive"))
    )
    (net (code "3") (name "/LAN0_B+") (class "Default")
      (node (ref "J6700") (pin "A3") (pinfunction "A3_A3") (pintype "passive"))
      (node (ref "U6700") (pin "20") (pinfunction "MX2+_20") (pintype "passive"))
    )
    (net (code "4") (name "/LAN0_B-") (class "Default")
      (node (ref "J6700") (pin "A6") (pinfunction "A6_A6") (pintype "passive"))
      (node (ref "U6700") (pin "19") (pinfunction "MX2-_19") (pintype "passive"))
    )
    (net (code "5") (name "/LAN0_C+") (class "Default")
      (node (ref "J6700") (pin "A4") (pinfunction "A4_A4") (pintype "passive"))
      (node (ref "U6700") (pin "17") (pinfunction "MX3+_17") (pintype "passive"))
    )
    (net (code "6") (name "/LAN0_C-") (class "Default")
      (node (ref "J6700") (pin "A5") (pinfunction "A5_A5") (pintype "passive"))
      (node (ref "U6700") (pin "16") (pinfunction "MX3-_16") (pintype "passive"))
    )
    (net (code "7") (name "/LAN0_D+") (class "Default")
      (node (ref "J6700") (pin "A7") (pinfunction "A7_A7") (pintype "passive"))
      (node (ref "U6700") (pin "14") (pinfunction "MX4+_14") (pintype "passive"))
    )
    (net (code "8") (name "/LAN0_D-") (class "Default")
      (node (ref "J6700") (pin "A8") (pinfunction "A8_A8") (pintype "passive"))
      (node (ref "U6700") (pin "13") (pinfunction "MX4-_13") (pintype "passive"))
    )
    (net (code "9") (name "/LAN0_MCT1") (class "Default")
      (node (ref "D6702") (pin "1") (pinfunction "1_1") (pintype "passive"))
      (node (ref "D6707") (pin "1") (pinfunction "1_1") (pintype "passive"))
      (node (ref "R6713") (pin "1") (pinfunction "1_1") (pintype "passive"))
      (node (ref "U6700") (pin "24") (pinfunction "MCT1_24") (pintype "passive"))
    )
    (net (code "10") (name "/LAN0_MCT2") (class "Default")
      (node (ref "D6700") (pin "1") (pinfunction "1_1") (pintype "passive"))
      (node (ref "D6704") (pin "1") (pinfunction "1_1") (pintype "passive"))
      (node (ref "R6712") (pin "1") (pinfunction "1_1") (pintype "passive"))
      (node (ref "U6700") (pin "21") (pinfunction "MCT2_21") (pintype "passive"))
    )
    (net (code "11") (name "/LAN0_MCT3") (class "Default")
      (node (ref "D6703") (pin "1") (pinfunction "1_1") (pintype "passive"))
      (node (ref "D6705") (pin "1") (pinfunction "1_1") (pintype "passive"))
      (node (ref "R6711") (pin "1") (pinfunction "1_1") (pintype "passive"))
      (node (ref "U6700") (pin "18") (pinfunction "MCT3_18") (pintype "passive"))
    )
    (net (code "12") (name "/LAN0_MCT4") (class "Default")
      (node (ref "D6701") (pin "1") (pinfunction "1_1") (pintype "passive"))
      (node (ref "D6706") (pin "1") (pinfunction "1_1") (pintype "passive"))
      (node (ref "R6710") (pin "1") (pinfunction "1_1") (pintype "passive"))
      (node (ref "U6700") (pin "15") (pinfunction "MCT4_15") (pintype "passive"))
    )
    (net (code "13") (name "/PHY0_CLKOUT125") (class "Default")
      (node (ref "R6714") (pin "2") (pinfunction "2_2") (pintype "passive"))
      (node (ref "U6701") (pin "35") (pinfunction "CLKOUT_35") (pintype "passive"))
    )
    (net (code "14") (name "/PHY0_LED0{slash}CFG_EXT") (class "Default")
      (node (ref "R6716") (pin "1") (pinfunction "1_1") (pintype "passive"))
      (node (ref "R6717") (pin "2") (pinfunction "2_2") (pintype "passive"))
      (node (ref "U6701") (pin "32") (pinfunction "LED0/CFG_EXT_32") (pintype "passive"))
    )
    (net (code "15") (name "/PHY0_LED1{slash}CFG_LDO0") (class "Default")
      (node (ref "R6720") (pin "1") (pinfunction "1_1") (pintype "passive"))
      (node (ref "U6701") (pin "33") (pinfunction "LED1/CFG_LDO0_33") (pintype "passive"))
    )
    (net (code "16") (name "/PHY0_LED2{slash}CFG_LDO1") (class "Default")
      (node (ref "R6718") (pin "1") (pinfunction "1_1") (pintype "passive"))
      (node (ref "R6719") (pin "2") (pinfunction "2_2") (pintype "passive"))
      (node (ref "U6701") (pin "34") (pinfunction "LED2/CFG_LDO1_34") (pintype "passive"))
    )
    (net (code "17") (name "/PHY0_MDI0+") (class "Default")
      (node (ref "R6700") (pin "1") (pinfunction "1_1") (pintype "passive"))
      (node (ref "U6701") (pin "1") (pinfunction "MDI[0]+_1") (pintype "passive"))
    )
    (net (code "18") (name "/PHY0_MDI0-") (class "Default")
      (node (ref "R6701") (pin "1") (pinfunction "1_1") (pintype "passive"))
      (node (ref "U6701") (pin "2") (pinfunction "MDI[0]-_2") (pintype "passive"))
    )
    (net (code "19") (name "/PHY0_MDI1+") (class "Default")
      (node (ref "R6703") (pin "1") (pinfunction "1_1") (pintype "passive"))
      (node (ref "U6701") (pin "4") (pinfunction "MDI[1]+_4") (pintype "passive"))
    )
    (net (code "20") (name "/PHY0_MDI1-") (class "Default")
      (node (ref "R6704") (pin "1") (pinfunction "1_1") (pintype "passive"))
      (node (ref "U6701") (pin "5") (pinfunction "MDI[1]-_5") (pintype "passive"))
    )
    (net (code "21") (name "/PHY0_MDI2+") (class "Default")
      (node (ref "R6705") (pin "1") (pinfunction "1_1") (pintype "passive"))
      (node (ref "U6701") (pin "6") (pinfunction "MDI[2]+_6") (pintype "passive"))
    )
    (net (code "22") (name "/PHY0_MDI2-") (class "Default")
      (node (ref "R6706") (pin "1") (pinfunction "1_1") (pintype "passive"))
      (node (ref "U6701") (pin "7") (pinfunction "MDI[2]-_7") (pintype "passive"))
    )
    (net (code "23") (name "/PHY0_MDI3+") (class "Default")
      (node (ref "R6707") (pin "1") (pinfunction "1_1") (pintype "passive"))
      (node (ref "U6701") (pin "9") (pinfunction "MDI[3]+_9") (pintype "passive"))
    )
    (net (code "24") (name "/PHY0_MDI3-") (class "Default")
      (node (ref "R6708") (pin "1") (pinfunction "1_1") (pintype "passive"))
      (node (ref "U6701") (pin "10") (pinfunction "MDI[3]-_10") (pintype "passive"))
    )
    (net (code "25") (name "/PHY0_MDI_0+") (class "Default")
      (node (ref "ED6703") (pin "2") (pinfunction "2_2") (pintype "passive"))
      (node (ref "R6700") (pin "2") (pinfunction "2_2") (pintype "passive"))
      (node (ref "U6700") (pin "2") (pinfunction "TD1+_2") (pintype "passive"))
    )
    (net (code "26") (name "/PHY0_MDI_0-") (class "Default")
      (node (ref "ED6703") (pin "1") (pinfunction "1_1") (pintype "passive"))
      (node (ref "R6701") (pin "2") (pinfunction "2_2") (pintype "passive"))
      (node (ref "U6700") (pin "3") (pinfunction "TD1-_3") (pintype "passive"))
    )
    (net (code "27") (name "/PHY0_MDI_1+") (class "Default")
      (node (ref "ED6702") (pin "2") (pinfunction "2_2") (pintype "passive"))
      (node (ref "R6703") (pin "2") (pinfunction "2_2") (pintype "passive"))
      (node (ref "U6700") (pin "5") (pinfunction "TD2+_5") (pintype "passive"))
    )
    (net (code "28") (name "/PHY0_MDI_1-") (class "Default")
      (node (ref "ED6702") (pin "1") (pinfunction "1_1") (pintype "passive"))
      (node (ref "R6704") (pin "2") (pinfunction "2_2") (pintype "passive"))
      (node (ref "U6700") (pin "6") (pinfunction "TD2-_6") (pintype "passive"))
    )
    (net (code "29") (name "/PHY0_MDI_2+") (class "Default")
      (node (ref "ED6701") (pin "2") (pinfunction "2_2") (pintype "passive"))
      (node (ref "R6705") (pin "2") (pinfunction "2_2") (pintype "passive"))
      (node (ref "U6700") (pin "8") (pinfunction "TD3+_8") (pintype "passive"))
    )
    (net (code "30") (name "/PHY0_MDI_2-") (class "Default")
      (node (ref "ED6701") (pin "1") (pinfunction "1_1") (pintype "passive"))
      (node (ref "R6706") (pin "2") (pinfunction "2_2") (pintype "passive"))
      (node (ref "U6700") (pin "9") (pinfunction "TD3-_9") (pintype "passive"))
    )
    (net (code "31") (name "/PHY0_MDI_3+") (class "Default")
      (node (ref "ED6700") (pin "2") (pinfunction "2_2") (pintype "passive"))
      (node (ref "R6707") (pin "2") (pinfunction "2_2") (pintype "passive"))
      (node (ref "U6700") (pin "11") (pinfunction "TD4+_11") (pintype "passive"))
    )
    (net (code "32") (name "/PHY0_MDI_3-") (class "Default")
      (node (ref "ED6700") (pin "1") (pinfunction "1_1") (pintype "passive"))
      (node (ref "R6708") (pin "2") (pinfunction "2_2") (pintype "passive"))
      (node (ref "U6700") (pin "12") (pinfunction "TD4-_12") (pintype "passive"))
    )
    (net (code "33") (name "/PHY0_REG_OUT") (class "Default")
      (node (ref "L6700") (pin "1") (pinfunction "1_1") (pintype "passive"))
      (node (ref "U6701") (pin "30") (pinfunction "REG_OUT_30") (pintype "passive"))
    )
    (net (code "34") (name "/PHY0_RSTn") (class "Default")
      (node (ref "C6718") (pin "1") (pinfunction "1_1") (pintype "passive"))
      (node (ref "R6734") (pin "2") (pinfunction "2_2") (pintype "passive"))
      (node (ref "R6736") (pin "2") (pinfunction "2_2") (pintype "passive"))
      (node (ref "U6701") (pin "12") (pinfunction "PHYRSTB_12") (pintype "passive"))
    )
    (net (code "35") (name "/PHY0_RXCLK{slash}PHYAD1") (class "Default")
      (node (ref "R6724") (pin "1") (pinfunction "1_1") (pintype "passive"))
      (node (ref "R6741") (pin "1") (pinfunction "1_1") (pintype "passive"))
      (node (ref "U6701") (pin "27") (pinfunction "RXC/PHYAD1_27") (pintype "passive"))
    )
    (net (code "36") (name "/PHY0_RXD0{slash}RXDLY") (class "Default")
      (node (ref "R6726") (pin "1") (pinfunction "1_1") (pintype "passive"))
      (node (ref "R6727") (pin "2") (pinfunction "2_2") (pintype "passive"))
      (node (ref "R6737") (pin "1") (pinfunction "1_1") (pintype "passive"))
      (node (ref "U6701") (pin "25") (pinfunction "RXD0/RXDLY_25") (pintype "passive"))
    )
    (net (code "37") (name "/PHY0_RXD1{slash}TXDLY") (class "Default")
      (node (ref "R6728") (pin "1") (pinfunction "1_1") (pintype "passive"))
      (node (ref "R6729") (pin "2") (pinfunction "2_2") (pintype "passive"))
      (node (ref "R6738") (pin "1") (pinfunction "1_1") (pintype "passive"))
      (node (ref "U6701") (pin "24") (pinfunction "RXD1/TXDLY_24") (pintype "passive"))
    )
    (net (code "38") (name "/PHY0_RXD2{slash}PLLOFF") (class "Default")
      (node (ref "R6731") (pin "1") (pinfunction "1_1") (pintype "passive"))
      (node (ref "R6732") (pin "2") (pinfunction "2_2") (pintype "passive"))
      (node (ref "R6739") (pin "1") (pinfunction "1_1") (pintype "passive"))
      (node (ref "U6701") (pin "23") (pinfunction "RXD2/PLLOFF_23") (pintype "passive"))
    )
    (net (code "39") (name "/PHY0_RXD3{slash}PHYAD0") (class "Default")
      (node (ref "R6722") (pin "1") (pinfunction "1_1") (pintype "passive"))
      (node (ref "R6723") (pin "2") (pinfunction "2_2") (pintype "passive"))
      (node (ref "R6740") (pin "1") (pinfunction "1_1") (pintype "passive"))
      (node (ref "U6701") (pin "22") (pinfunction "RXD3/PHYAD0_22") (pintype "passive"))
    )
    (net (code "40") (name "/PHY0_RXDV{slash}PHYAD2") (class "Default")
      (node (ref "R6725") (pin "1") (pinfunction "1_1") (pintype "passive"))
      (node (ref "R6742") (pin "1") (pinfunction "1_1") (pintype "passive"))
      (node (ref "U6701") (pin "26") (pinfunction "RXCTL/PHYAD2_26") (pintype "passive"))
    )
    (net (code "41") (name "/PHY0_XTALIN") (class "Default")
      (node (ref "C6701") (pin "1") (pinfunction "1_1") (pintype "passive"))
      (node (ref "R6702") (pin "1") (pinfunction "1_1") (pintype "passive"))
      (node (ref "U6701") (pin "36") (pinfunction "XTAL_IN_36") (pintype "passive"))
      (node (ref "Y6700") (pin "3") (pinfunction "X2_3") (pintype "passive"))
    )
    (net (code "42") (name "/PHY0_XTALOUT") (class "Default")
      (node (ref "C6700") (pin "1") (pinfunction "1_1") (pintype "passive"))
      (node (ref "R6709") (pin "2") (pinfunction "2_2") (pintype "passive"))
      (node (ref "U6701") (pin "37") (pinfunction "XTAL_OUT/EXT_CLK_37") (pintype "passive"))
      (node (ref "Y6700") (pin "1") (pinfunction "X1_1") (pintype "passive"))
    )
    (net (code "43") (name "/RSET0") (class "Default")
      (node (ref "R6721") (pin "1") (pinfunction "1_1") (pintype "passive"))
      (node (ref "U6701") (pin "39") (pinfunction "RSET_39") (pintype "passive"))
    )
    (net (code "44") (name "ETH0_REFCLKO_25M") (class "Default")
      (node (ref "R6709") (pin "1") (pinfunction "1_1") (pintype "passive"))
    )
    (net (code "45") (name "GMAC0_MCLKINOUT") (class "Default")
      (node (ref "C6706") (pin "1") (pinfunction "1_1") (pintype "passive"))
      (node (ref "R6714") (pin "1") (pinfunction "1_1") (pintype "passive"))
      (node (ref "R6715") (pin "1") (pinfunction "1_1") (pintype "passive"))
    )
    (net (code "46") (name "GMAC0_MDC") (class "Default")
      (node (ref "U6701") (pin "13") (pinfunction "MDC_13") (pintype "passive"))
    )
    (net (code "47") (name "GMAC0_MDIO") (class "Default")
      (node (ref "R6735") (pin "2") (pinfunction "2_2") (pintype "passive"))
      (node (ref "U6701") (pin "14") (pinfunction "MDIO_14") (pintype "passive"))
    )
    (net (code "48") (name "GMAC0_RSTn_L_GPIO4_B3") (class "Default")
      (node (ref "R6736") (pin "1") (pinfunction "1_1") (pintype "passive"))
    )
    (net (code "49") (name "GMAC0_RXCLK") (class "Default")
      (node (ref "C6724") (pin "1") (pinfunction "1_1") (pintype "passive"))
      (node (ref "R6741") (pin "2") (pinfunction "2_2") (pintype "passive"))
    )
    (net (code "50") (name "GMAC0_RXD0") (class "Default")
      (node (ref "R6737") (pin "2") (pinfunction "2_2") (pintype "passive"))
    )
    (net (code "51") (name "GMAC0_RXD1") (class "Default")
      (node (ref "R6738") (pin "2") (pinfunction "2_2") (pintype "passive"))
    )
    (net (code "52") (name "GMAC0_RXD2") (class "Default")
      (node (ref "R6739") (pin "2") (pinfunction "2_2") (pintype "passive"))
    )
    (net (code "53") (name "GMAC0_RXD3") (class "Default")
      (node (ref "R6740") (pin "2") (pinfunction "2_2") (pintype "passive"))
    )
    (net (code "54") (name "GMAC0_RXDV_CRS") (class "Default")
      (node (ref "R6742") (pin "2") (pinfunction "2_2") (pintype "passive"))
    )
    (net (code "55") (name "GMAC0_TXCLK") (class "Default")
      (node (ref "C6726") (pin "1") (pinfunction "1_1") (pintype "passive"))
      (node (ref "U6701") (pin "20") (pinfunction "TXC_20") (pintype "passive"))
    )
    (net (code "56") (name "GMAC0_TXD0") (class "Default")
      (node (ref "U6701") (pin "18") (pinfunction "TXD0_18") (pintype "passive"))
    )
    (net (code "57") (name "GMAC0_TXD1") (class "Default")
      (node (ref "U6701") (pin "17") (pinfunction "TXD1_17") (pintype "passive"))
    )
    (net (code "58") (name "GMAC0_TXD2") (class "Default")
      (node (ref "U6701") (pin "16") (pinfunction "TXD2_16") (pintype "passive"))
    )
    (net (code "59") (name "GMAC0_TXD3") (class "Default")
      (node (ref "U6701") (pin "15") (pinfunction "TXD3_15") (pintype "passive"))
    )
    (net (code "60") (name "GMAC0_TXEN") (class "Default")
      (node (ref "U6701") (pin "19") (pinfunction "TXCTL_19") (pintype "passive"))
    )
    (net (code "61") (name "GND") (class "Default")
      (node (ref "C6700") (pin "2") (pinfunction "2_2") (pintype "passive"))
      (node (ref "C6701") (pin "2") (pinfunction "2_2") (pintype "passive"))
      (node (ref "C6702") (pin "2") (pinfunction "2_2") (pintype "passive"))
      (node (ref "C6703") (pin "2") (pinfunction "2_2") (pintype "passive"))
      (node (ref "C6704") (pin "2") (pinfunction "2_2") (pintype "passive"))
      (node (ref "C6705") (pin "2") (pinfunction "2_2") (pintype "passive"))
      (node (ref "C6706") (pin "2") (pinfunction "2_2") (pintype "passive"))
      (node (ref "C6707") (pin "2") (pinfunction "2_2") (pintype "passive"))
      (node (ref "C6708") (pin "2") (pinfunction "2_2") (pintype "passive"))
      (node (ref "C6709") (pin "2") (pinfunction "2_2") (pintype "passive"))
      (node (ref "C6710") (pin "2") (pinfunction "2_2") (pintype "passive"))
      (node (ref "C6711") (pin "2") (pinfunction "2_2") (pintype "passive"))
      (node (ref "C6712") (pin "2") (pinfunction "2_2") (pintype "passive"))
      (node (ref "C6713") (pin "2") (pinfunction "2_2") (pintype "passive"))
      (node (ref "C6714") (pin "2") (pinfunction "2_2") (pintype "passive"))
      (node (ref "C6715") (pin "2") (pinfunction "2_2") (pintype "passive"))
      (node (ref "C6716") (pin "2") (pinfunction "2_2") (pintype "passive"))
      (node (ref "C6717") (pin "2") (pinfunction "2_2") (pintype "passive"))
      (node (ref "C6718") (pin "2") (pinfunction "2_2") (pintype "passive"))
      (node (ref "C6719") (pin "2") (pinfunction "2_2") (pintype "passive"))
      (node (ref "C6720") (pin "2") (pinfunction "2_2") (pintype "passive"))
      (node (ref "C6721") (pin "2") (pinfunction "2_2") (pintype "passive"))
      (node (ref "C6722") (pin "2") (pinfunction "2_2") (pintype "passive"))
      (node (ref "C6723") (pin "2") (pinfunction "2_2") (pintype "passive"))
      (node (ref "C6724") (pin "2") (pinfunction "2_2") (pintype "passive"))
      (node (ref "C6726") (pin "2") (pinfunction "2_2") (pintype "passive"))
      (node (ref "D6700") (pin "2") (pinfunction "2_2") (pintype "passive"))
      (node (ref "D6701") (pin "2") (pinfunction "2_2") (pintype "passive"))
      (node (ref "D6702") (pin "2") (pinfunction "2_2") (pintype "passive"))
      (node (ref "D6703") (pin "2") (pinfunction "2_2") (pintype "passive"))
      (node (ref "D6704") (pin "2") (pinfunction "2_2") (pintype "passive"))
      (node (ref "D6705") (pin "2") (pinfunction "2_2") (pintype "passive"))
      (node (ref "D6706") (pin "2") (pinfunction "2_2") (pintype "passive"))
      (node (ref "D6707") (pin "2") (pinfunction "2_2") (pintype "passive"))
      (node (ref "FB6700") (pin "1") (pinfunction "1_1") (pintype "passive"))
      (node (ref "R6702") (pin "2") (pinfunction "2_2") (pintype "passive"))
      (node (ref "R6715") (pin "2") (pinfunction "2_2") (pintype "passive"))
      (node (ref "R6716") (pin "2") (pinfunction "2_2") (pintype "passive"))
      (node (ref "R6718") (pin "2") (pinfunction "2_2") (pintype "passive"))
      (node (ref "R6720") (pin "2") (pinfunction "2_2") (pintype "passive"))
      (node (ref "R6721") (pin "2") (pinfunction "2_2") (pintype "passive"))
      (node (ref "R6722") (pin "2") (pinfunction "2_2") (pintype "passive"))
      (node (ref "R6724") (pin "2") (pinfunction "2_2") (pintype "passive"))
      (node (ref "R6725") (pin "2") (pinfunction "2_2") (pintype "passive"))
      (node (ref "R6726") (pin "2") (pinfunction "2_2") (pintype "passive"))
      (node (ref "R6728") (pin "2") (pinfunction "2_2") (pintype "passive"))
      (node (ref "R6731") (pin "2") (pinfunction "2_2") (pintype "passive"))
      (node (ref "U6701") (pin "41") (pinfunction "E_Pad_41") (pintype "passive"))
      (node (ref "Y6700") (pin "2") (pinfunction "GND_2") (pintype "power_in"))
      (node (ref "Y6700") (pin "4") (pinfunction "GND_4") (pintype "power_in"))
    )
    (net (code "62") (name "LAN1_A+") (class "Default")
      (node (ref "J6700") (pin "B1") (pinfunction "B1_B1") (pintype "passive"))
    )
    (net (code "63") (name "LAN1_A-") (class "Default")
      (node (ref "J6700") (pin "B2") (pinfunction "B2_B2") (pintype "passive"))
    )
    (net (code "64") (name "LAN1_B+") (class "Default")
      (node (ref "J6700") (pin "B3") (pinfunction "B3_B3") (pintype "passive"))
    )
    (net (code "65") (name "LAN1_B-") (class "Default")
      (node (ref "J6700") (pin "B6") (pinfunction "B6_B6") (pintype "passive"))
    )
    (net (code "66") (name "LAN1_C+") (class "Default")
      (node (ref "J6700") (pin "B4") (pinfunction "B4_B4") (pintype "passive"))
    )
    (net (code "67") (name "LAN1_C-") (class "Default")
      (node (ref "J6700") (pin "B5") (pinfunction "B5_B5") (pintype "passive"))
    )
    (net (code "68") (name "LAN1_D+") (class "Default")
      (node (ref "J6700") (pin "B7") (pinfunction "B7_B7") (pintype "passive"))
    )
    (net (code "69") (name "LAN1_D-") (class "Default")
      (node (ref "J6700") (pin "B8") (pinfunction "B8_B8") (pintype "passive"))
    )
    (net (code "70") (name "Net-(C6707-Pad1)") (class "Default")
      (node (ref "C6707") (pin "1") (pinfunction "1_1") (pintype "passive"))
      (node (ref "R6710") (pin "2") (pinfunction "2_2") (pintype "passive"))
      (node (ref "R6711") (pin "2") (pinfunction "2_2") (pintype "passive"))
      (node (ref "R6712") (pin "2") (pinfunction "2_2") (pintype "passive"))
      (node (ref "R6713") (pin "2") (pinfunction "2_2") (pintype "passive"))
    )
    (net (code "71") (name "Net-(J6700-G1)") (class "Default")
      (node (ref "C6708") (pin "1") (pinfunction "1_1") (pintype "passive"))
      (node (ref "FB6700") (pin "2") (pinfunction "2_2") (pintype "passive"))
      (node (ref "J6700") (pin "1") (pinfunction "G1_1") (pintype "passive"))
      (node (ref "J6700") (pin "2") (pinfunction "G2_2") (pintype "passive"))
      (node (ref "J6700") (pin "3") (pinfunction "G3_3") (pintype "passive"))
      (node (ref "J6700") (pin "4") (pinfunction "G4_4") (pintype "passive"))
    )
    (net (code "72") (name "Net-(U6700-TCT1)") (class "Default")
      (node (ref "C6702") (pin "1") (pinfunction "1_1") (pintype "passive"))
      (node (ref "C6703") (pin "1") (pinfunction "1_1") (pintype "passive"))
      (node (ref "C6704") (pin "1") (pinfunction "1_1") (pintype "passive"))
      (node (ref "C6705") (pin "1") (pinfunction "1_1") (pintype "passive"))
      (node (ref "U6700") (pin "1") (pinfunction "TCT1_1") (pintype "passive"))
      (node (ref "U6700") (pin "10") (pinfunction "TCT4_10") (pintype "passive"))
      (node (ref "U6700") (pin "4") (pinfunction "TCT2_4") (pintype "passive"))
      (node (ref "U6700") (pin "7") (pinfunction "TCT3_7") (pintype "passive"))
    )
    (net (code "73") (name "Net-(U6701-INTB{slash}PMEB)") (class "Default")
      (node (ref "TP6700") (pin "1") (pinfunction "1_1") (pintype "passive"))
      (node (ref "U6701") (pin "31") (pinfunction "INTB/PMEB_31") (pintype "passive"))
    )
    (net (code "74") (name "VCC3V3_PHY0") (class "Default")
      (node (ref "C6712") (pin "1") (pinfunction "1_1") (pintype "passive"))
      (node (ref "C6713") (pin "1") (pinfunction "1_1") (pintype "passive"))
      (node (ref "C6714") (pin "1") (pinfunction "1_1") (pintype "passive"))
      (node (ref "C6719") (pin "1") (pinfunction "1_1") (pintype "passive"))
      (node (ref "C6720") (pin "1") (pinfunction "1_1") (pintype "passive"))
      (node (ref "R6717") (pin "1") (pinfunction "1_1") (pintype "passive"))
      (node (ref "R6719") (pin "1") (pinfunction "1_1") (pintype "passive"))
      (node (ref "R6733") (pin "2") (pinfunction "2_2") (pintype "passive"))
      (node (ref "R6734") (pin "1") (pinfunction "1_1") (pintype "passive"))
      (node (ref "U6701") (pin "11") (pinfunction "AVDD33_11") (pintype "power_in"))
      (node (ref "U6701") (pin "29") (pinfunction "DVDD33_29") (pintype "power_in"))
      (node (ref "U6701") (pin "40") (pinfunction "AVDD33_40") (pintype "power_in"))
    )
    (net (code "75") (name "VCCIO_PHY0") (class "Default")
      (node (ref "C6709") (pin "1") (pinfunction "1_1") (pintype "passive"))
      (node (ref "C6710") (pin "1") (pinfunction "1_1") (pintype "passive"))
      (node (ref "C6711") (pin "1") (pinfunction "1_1") (pintype "passive"))
      (node (ref "R6723") (pin "1") (pinfunction "1_1") (pintype "passive"))
      (node (ref "R6727") (pin "1") (pinfunction "1_1") (pintype "passive"))
      (node (ref "R6729") (pin "1") (pinfunction "1_1") (pintype "passive"))
      (node (ref "R6730") (pin "2") (pinfunction "2_2") (pintype "passive"))
      (node (ref "R6732") (pin "1") (pinfunction "1_1") (pintype "passive"))
      (node (ref "R6735") (pin "1") (pinfunction "1_1") (pintype "passive"))
      (node (ref "U6701") (pin "28") (pinfunction "DVDD_RG_28") (pintype "passive"))
    )
    (net (code "76") (name "VCC_1V8") (class "Default")
      (node (ref "R6730") (pin "1") (pinfunction "1_1") (pintype "passive"))
    )
    (net (code "77") (name "VCC_3V3") (class "Default")
      (node (ref "R6733") (pin "1") (pinfunction "1_1") (pintype "passive"))
    )
    (net (code "78") (name "VDD10_PHY0") (class "Default")
      (node (ref "C6715") (pin "1") (pinfunction "1_1") (pintype "passive"))
      (node (ref "C6716") (pin "1") (pinfunction "1_1") (pintype "passive"))
      (node (ref "C6717") (pin "1") (pinfunction "1_1") (pintype "passive"))
      (node (ref "C6721") (pin "1") (pinfunction "1_1") (pintype "passive"))
      (node (ref "C6722") (pin "1") (pinfunction "1_1") (pintype "passive"))
      (node (ref "C6723") (pin "1") (pinfunction "1_1") (pintype "passive"))
      (node (ref "L6700") (pin "2") (pinfunction "2_2") (pintype "passive"))
      (node (ref "U6701") (pin "21") (pinfunction "DVDD10_21") (pintype "power_in"))
      (node (ref "U6701") (pin "3") (pinfunction "AVDD10_3") (pintype "power_in"))
      (node (ref "U6701") (pin "38") (pinfunction "AVDD10_38") (pintype "power_in"))
      (node (ref "U6701") (pin "8") (pinfunction "AVDD10_8") (pintype "power_in"))
    )
  )
)
